# MCX_Mezzanine.net
KiCad netlist of a schematic drawn in Altium Designer
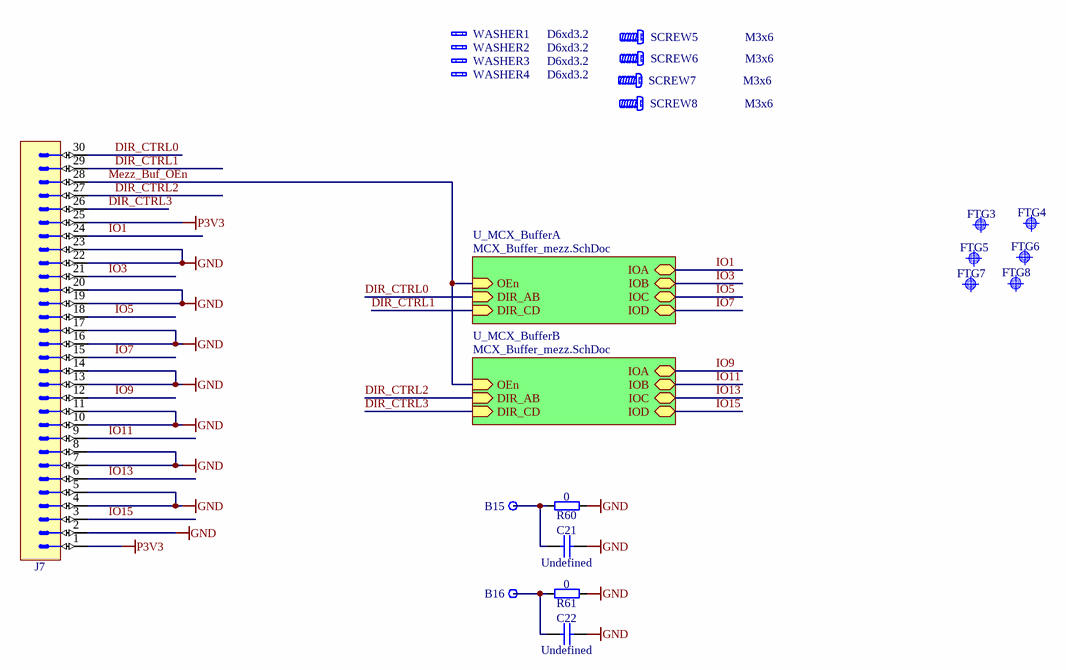
[diagram p0: MCX_Mezzanine.SchDoc]

(export (version "E")
  (design (tool "Eeschema 10.0.6"))
  (components
    (comp (ref "B15")
      (value "Plated Hole")
      (footprint "MTG270_500")
      (description "Single Terminal Socket")
      (fields (field (name "PART NUMBER") "PLATED_HOLE2.7_PAD5.0") (field (name "AUTHOR") "CERN DEM JMW"))
      (libsource (lib "Eletro-mechanical") (part "Single Terminal Socket"))
    )
    (comp (ref "B16")
      (value "Plated Hole")
      (footprint "MTG270_500")
      (description "Single Terminal Socket")
      (fields (field (name "PART NUMBER") "PLATED_HOLE2.7_PAD5.0") (field (name "AUTHOR") "CERN DEM JMW"))
      (libsource (lib "Eletro-mechanical") (part "Single Terminal Socket"))
    )
    (comp (ref "C21")
      (value "Undefined")
      (footprint "CAPC2012X135N")
      (description "Non-polarised capacitor")
      (fields (field (name "PART NUMBER") "CC0805_NO-VALUE") (field (name "AUTHOR") "CERN DEM JLC"))
      (libsource (lib "Capacitors") (part "Capacitor - non polarized"))
    )
    (comp (ref "C22")
      (value "Undefined")
      (footprint "CAPC2012X135N")
      (description "Non-polarised capacitor")
      (fields (field (name "PART NUMBER") "CC0805_NO-VALUE") (field (name "AUTHOR") "CERN DEM JLC"))
      (libsource (lib "Capacitors") (part "Capacitor - non polarized"))
    )
    (comp (ref "FTG3")
      (value "Use only in PCB")
      (footprint "FIDUCIAL_TOP_S100-200")
      (description "Fiducial Target")
      (fields (field (name "PART NUMBER") "FIDUCIAL_TARGET_S100-200") (field (name "AUTHOR") "CERN DEM JLC"))
      (libsource (lib "Eletro-mechanical") (part "Fiducial Target"))
    )
    (comp (ref "FTG4")
      (value "Use only in PCB")
      (footprint "FIDUCIAL_TOP_C100-200")
      (description "Fiducial Target")
      (fields (field (name "PART NUMBER") "FIDUCIAL_TARGET_C100-200") (field (name "AUTHOR") "CERN DEM JLC"))
      (libsource (lib "Eletro-mechanical") (part "Fiducial Target"))
    )
    (comp (ref "FTG5")
      (value "Use only in PCB")
      (footprint "FIDUCIAL_TOP_S100-200")
      (description "Fiducial Target")
      (fields (field (name "PART NUMBER") "FIDUCIAL_TARGET_S100-200") (field (name "AUTHOR") "CERN DEM JLC"))
      (libsource (lib "Eletro-mechanical") (part "Fiducial Target"))
    )
    (comp (ref "FTG6")
      (value "Use only in PCB")
      (footprint "FIDUCIAL_TOP_C100-200")
      (description "Fiducial Target")
      (fields (field (name "PART NUMBER") "FIDUCIAL_TARGET_C100-200") (field (name "AUTHOR") "CERN DEM JLC"))
      (libsource (lib "Eletro-mechanical") (part "Fiducial Target"))
    )
    (comp (ref "FTG7")
      (value "Use only in PCB")
      (footprint "FIDUCIAL_TOP_C100-200")
      (description "Fiducial Target")
      (fields (field (name "PART NUMBER") "FIDUCIAL_TARGET_C100-200") (field (name "AUTHOR") "CERN DEM JLC"))
      (libsource (lib "Eletro-mechanical") (part "Fiducial Target"))
    )
    (comp (ref "FTG8")
      (value "Use only in PCB")
      (footprint "FIDUCIAL_TOP_S100-200")
      (description "Fiducial Target")
      (fields (field (name "PART NUMBER") "FIDUCIAL_TARGET_S100-200") (field (name "AUTHOR") "CERN DEM JLC"))
      (libsource (lib "Eletro-mechanical") (part "Fiducial Target"))
    )
    (comp (ref "J7")
      (value "AMPMODU")
      (footprint "TYCO_1-215307-5")
      (description "Connector 2.54mm, 30 pin female, vertical, 7mm, AMPMODU HV-100/HV-190")
      (fields
        (field (name "PART NUMBER") "TYCO_1-215307-5")
        (field (name "MANUFACTURER") "TYCO ELECTRONICS")
        (field (name "AUTHOR") "GK")
      )
      (libsource (lib "LIBRARY_SCH") (part "CON_2x15_2.54_female_V_mirror"))
    )
    (comp (ref "R60")
      (value "0")
      (footprint "RESC1608X55N")
      (description "Resistor")
      (fields
        (field (name "PART NUMBER") "R0603_0R_JUMPER")
        (field (name "MANUFACTURER") "GENERIC")
        (field (name "AUTHOR") "CERN DEM JLC")
      )
      (libsource (lib "Resistors") (part "Resistor"))
    )
    (comp (ref "R61")
      (value "0")
      (footprint "RESC1608X55N")
      (description "Resistor")
      (fields
        (field (name "PART NUMBER") "R0603_0R_JUMPER")
        (field (name "MANUFACTURER") "GENERIC")
        (field (name "AUTHOR") "CERN DEM JLC")
      )
      (libsource (lib "Resistors") (part "Resistor"))
    )
    (comp (ref "SCREW5")
      (value "M3x6")
      (footprint "BOSSARD_BN5687-3061605_v")
      (description "Screw")
      (fields
        (field (name "PART NUMBER") "BOSSARD_BN5687-3061605_v")
        (field (name "MANUFACTURER") "BOSSARD")
        (field (name "AUTHOR") "CERN DEM JLC")
      )
      (libsource (lib "Eletro-mechanical") (part "Screw"))
    )
    (comp (ref "SCREW6")
      (value "M3x6")
      (footprint "BOSSARD_BN5687-3061605_v")
      (description "Screw")
      (fields
        (field (name "PART NUMBER") "BOSSARD_BN5687-3061605_v")
        (field (name "MANUFACTURER") "BOSSARD")
        (field (name "AUTHOR") "CERN DEM JLC")
      )
      (libsource (lib "Eletro-mechanical") (part "Screw"))
    )
    (comp (ref "SCREW7")
      (value "M3x6")
      (footprint "BOSSARD_BN5687-3061605_v")
      (description "Screw")
      (fields
        (field (name "PART NUMBER") "BOSSARD_BN5687-3061605_v")
        (field (name "MANUFACTURER") "BOSSARD")
        (field (name "AUTHOR") "CERN DEM JLC")
      )
      (libsource (lib "Eletro-mechanical") (part "Screw"))
    )
    (comp (ref "SCREW8")
      (value "M3x6")
      (footprint "BOSSARD_BN5687-3061605_v")
      (description "Screw")
      (fields
        (field (name "PART NUMBER") "BOSSARD_BN5687-3061605_v")
        (field (name "MANUFACTURER") "BOSSARD")
        (field (name "AUTHOR") "CERN DEM JLC")
      )
      (libsource (lib "Eletro-mechanical") (part "Screw"))
    )
    (comp (ref "WASHER1")
      (value "D6xd3.2")
      (footprint "BOSSARD_B3/6/0.3/BN1976_v")
      (description "Washer, M3x0.3x6")
      (fields
        (field (name "PART NUMBER") "BOSSARD_B3/6/0.3/BN1976")
        (field (name "MANUFACTURER") "BOSSARD")
        (field (name "AUTHOR") "GK")
      )
      (libsource (lib "Mechanical") (part "MECH_Washer_M3x0.3x6"))
    )
    (comp (ref "WASHER2")
      (value "D6xd3.2")
      (footprint "BOSSARD_B3/6/0.3/BN1976_v")
      (description "Washer, M3x0.3x6")
      (fields
        (field (name "PART NUMBER") "BOSSARD_B3/6/0.3/BN1976")
        (field (name "MANUFACTURER") "BOSSARD")
        (field (name "AUTHOR") "GK")
      )
      (libsource (lib "Mechanical") (part "MECH_Washer_M3x0.3x6"))
    )
    (comp (ref "WASHER3")
      (value "D6xd3.2")
      (footprint "BOSSARD_B3/6/0.3/BN1976_v")
      (description "Washer, M3x0.3x6")
      (fields
        (field (name "PART NUMBER") "BOSSARD_B3/6/0.3/BN1976")
        (field (name "MANUFACTURER") "BOSSARD")
        (field (name "AUTHOR") "GK")
      )
      (libsource (lib "Mechanical") (part "MECH_Washer_M3x0.3x6"))
    )
    (comp (ref "WASHER4")
      (value "D6xd3.2")
      (footprint "BOSSARD_B3/6/0.3/BN1976_v")
      (description "Washer, M3x0.3x6")
      (fields
        (field (name "PART NUMBER") "BOSSARD_B3/6/0.3/BN1976")
        (field (name "MANUFACTURER") "BOSSARD")
        (field (name "AUTHOR") "GK")
      )
      (libsource (lib "Mechanical") (part "MECH_Washer_M3x0.3x6"))
    )
  )
  (nets
    (net (code "1") (name "/DIR_CTRL0") (class "Default")
      (node (ref "J7") (pin "30") (pinfunction "30_30") (pintype "bidirectional"))
    )
    (net (code "2") (name "/DIR_CTRL1") (class "Default")
      (node (ref "J7") (pin "29") (pinfunction "29_29") (pintype "bidirectional"))
    )
    (net (code "3") (name "/DIR_CTRL2") (class "Default")
      (node (ref "J7") (pin "27") (pinfunction "27_27") (pintype "bidirectional"))
    )
    (net (code "4") (name "/DIR_CTRL3") (class "Default")
      (node (ref "J7") (pin "26") (pinfunction "26_26") (pintype "bidirectional"))
    )
    (net (code "5") (name "/IO1") (class "Default")
      (node (ref "J7") (pin "24") (pinfunction "24_24") (pintype "bidirectional"))
    )
    (net (code "6") (name "/IO3") (class "Default")
      (node (ref "J7") (pin "21") (pinfunction "21_21") (pintype "bidirectional"))
    )
    (net (code "7") (name "/IO5") (class "Default")
      (node (ref "J7") (pin "18") (pinfunction "18_18") (pintype "bidirectional"))
    )
    (net (code "8") (name "/IO7") (class "Default")
      (node (ref "J7") (pin "15") (pinfunction "15_15") (pintype "bidirectional"))
    )
    (net (code "9") (name "/IO9") (class "Default")
      (node (ref "J7") (pin "12") (pinfunction "12_12") (pintype "bidirectional"))
    )
    (net (code "10") (name "/IO11") (class "Default")
      (node (ref "J7") (pin "9") (pinfunction "9_9") (pintype "bidirectional"))
    )
    (net (code "11") (name "/IO13") (class "Default")
      (node (ref "J7") (pin "6") (pinfunction "6_6") (pintype "bidirectional"))
    )
    (net (code "12") (name "/IO15") (class "Default")
      (node (ref "J7") (pin "3") (pinfunction "3_3") (pintype "bidirectional"))
    )
    (net (code "13") (name "/Mezz_Buf_OEn") (class "Default")
      (node (ref "J7") (pin "28") (pinfunction "28_28") (pintype "bidirectional"))
    )
    (net (code "14") (name "GND") (class "Default")
      (node (ref "C21") (pin "2") (pinfunction "2_2") (pintype "passive"))
      (node (ref "C22") (pin "2") (pinfunction "2_2") (pintype "passive"))
      (node (ref "J7") (pin "10") (pinfunction "10_10") (pintype "bidirectional"))
      (node (ref "J7") (pin "11") (pinfunction "11_11") (pintype "bidirectional"))
      (node (ref "J7") (pin "13") (pinfunction "13_13") (pintype "bidirectional"))
      (node (ref "J7") (pin "14") (pinfunction "14_14") (pintype "bidirectional"))
      (node (ref "J7") (pin "16") (pinfunction "16_16") (pintype "bidirectional"))
      (node (ref "J7") (pin "17") (pinfunction "17_17") (pintype "bidirectional"))
      (node (ref "J7") (pin "19") (pinfunction "19_19") (pintype "bidirectional"))
      (node (ref "J7") (pin "2") (pinfunction "2_2") (pintype "bidirectional"))
      (node (ref "J7") (pin "20") (pinfunction "20_20") (pintype "bidirectional"))
      (node (ref "J7") (pin "22") (pinfunction "22_22") (pintype "bidirectional"))
      (node (ref "J7") (pin "23") (pinfunction "23_23") (pintype "bidirectional"))
      (node (ref "J7") (pin "4") (pinfunction "4_4") (pintype "bidirectional"))
      (node (ref "J7") (pin "5") (pinfunction "5_5") (pintype "bidirectional"))
      (node (ref "J7") (pin "7") (pinfunction "7_7") (pintype "bidirectional"))
      (node (ref "J7") (pin "8") (pinfunction "8_8") (pintype "bidirectional"))
      (node (ref "R60") (pin "1") (pinfunction "1_1") (pintype "passive"))
      (node (ref "R61") (pin "1") (pinfunction "1_1") (pintype "passive"))
    )
    (net (code "15") (name "Net-(B15-Pad1)") (class "Default")
      (node (ref "B15") (pin "1") (pinfunction "1_1") (pintype "bidirectional"))
      (node (ref "C21") (pin "1") (pinfunction "1_1") (pintype "passive"))
      (node (ref "R60") (pin "2") (pinfunction "2_2") (pintype "passive"))
    )
    (net (code "16") (name "Net-(B16-Pad1)") (class "Default")
      (node (ref "B16") (pin "1") (pinfunction "1_1") (pintype "bidirectional"))
      (node (ref "C22") (pin "1") (pinfunction "1_1") (pintype "passive"))
      (node (ref "R61") (pin "2") (pinfunction "2_2") (pintype "passive"))
    )
    (net (code "17") (name "P3V3") (class "Default")
      (node (ref "J7") (pin "1") (pinfunction "1_1") (pintype "bidirectional"))
      (node (ref "J7") (pin "25") (pinfunction "25_25") (pintype "bidirectional"))
    )
  )
)
